# ARTIC_R2_Module.net
KiCad netlist of a schematic drawn in EAGLE
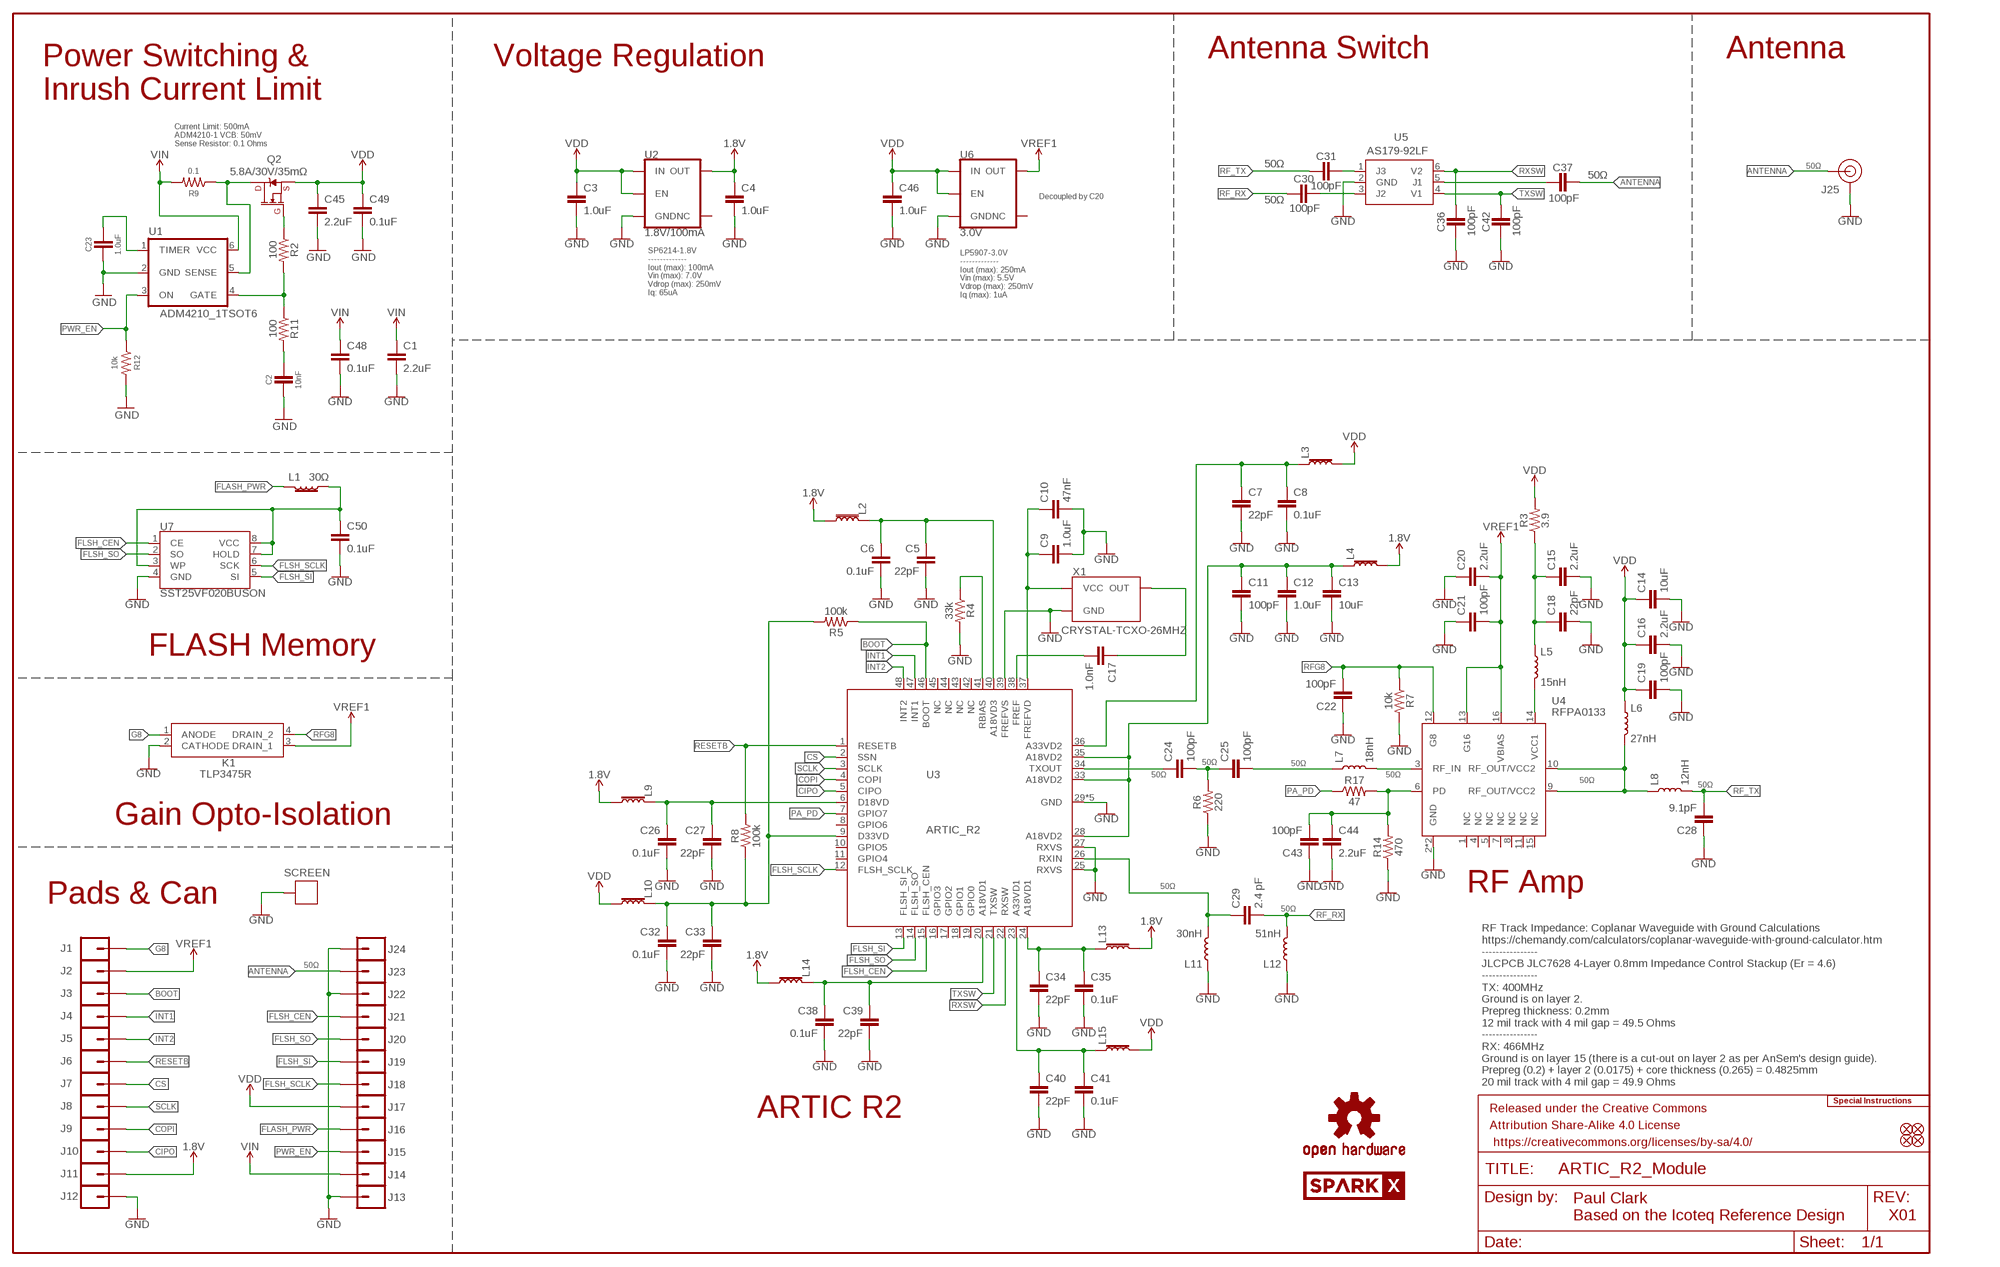
[diagram p0: schematic, sheet 1]

(export (version "E")
  (design (tool "Eeschema 10.0.6"))
  (components
    (comp (ref "C1")
      (value "2.2uF")
      (footprint "eagle-import:0402-TIGHT")
      (libsource (lib "eagle-import") (part "2.2UF-0402_TIGHT-10V-10%-X5R"))
    )
    (comp (ref "C2")
      (value "10nF")
      (footprint "eagle-import:0402-TIGHT")
      (libsource (lib "eagle-import") (part "10NF-0402T-25V-10%"))
    )
    (comp (ref "C3")
      (value "1.0uF")
      (footprint "eagle-import:0402-TIGHT")
      (libsource (lib "eagle-import") (part "1.0UF-0402T-16V-10%"))
    )
    (comp (ref "C4")
      (value "1.0uF")
      (footprint "eagle-import:0402-TIGHT")
      (libsource (lib "eagle-import") (part "1.0UF-0402T-16V-10%"))
    )
    (comp (ref "C5")
      (value "22pF")
      (footprint "eagle-import:0402-TIGHT")
      (libsource (lib "eagle-import") (part "22PF-0402T-16V-10%"))
    )
    (comp (ref "C6")
      (value "0.1uF")
      (footprint "eagle-import:0402-TIGHT")
      (libsource (lib "eagle-import") (part "0.1UF-0402T-6.3V-10%-X7R"))
    )
    (comp (ref "C7")
      (value "22pF")
      (footprint "eagle-import:0402-TIGHT")
      (libsource (lib "eagle-import") (part "22PF-0402T-16V-10%"))
    )
    (comp (ref "C8")
      (value "0.1uF")
      (footprint "eagle-import:0402-TIGHT")
      (libsource (lib "eagle-import") (part "0.1UF-0402T-6.3V-10%-X7R"))
    )
    (comp (ref "C9")
      (value "1.0uF")
      (footprint "eagle-import:0402-TIGHT")
      (libsource (lib "eagle-import") (part "1.0UF-0402T-16V-10%"))
    )
    (comp (ref "C10")
      (value "47nF")
      (footprint "eagle-import:0402-TIGHT")
      (libsource (lib "eagle-import") (part "47NF-0402_TIGHT-25V-10%-X7R"))
    )
    (comp (ref "C11")
      (value "100pF")
      (footprint "eagle-import:0402-TIGHT")
      (libsource (lib "eagle-import") (part "100PF-0402T-50V-5%"))
    )
    (comp (ref "C12")
      (value "1.0uF")
      (footprint "eagle-import:0402-TIGHT")
      (libsource (lib "eagle-import") (part "1.0UF-0402T-16V-10%"))
    )
    (comp (ref "C13")
      (value "10uF")
      (footprint "eagle-import:0402-TIGHT")
      (libsource (lib "eagle-import") (part "10UF-0402T-6.3V-20%"))
    )
    (comp (ref "C14")
      (value "10uF")
      (footprint "eagle-import:0402-TIGHT")
      (libsource (lib "eagle-import") (part "10UF-0402T-6.3V-20%"))
    )
    (comp (ref "C15")
      (value "2.2uF")
      (footprint "eagle-import:0402-TIGHT")
      (libsource (lib "eagle-import") (part "2.2UF-0402_TIGHT-10V-10%-X5R"))
    )
    (comp (ref "C16")
      (value "2.2uF")
      (footprint "eagle-import:0402-TIGHT")
      (libsource (lib "eagle-import") (part "2.2UF-0402_TIGHT-10V-10%-X5R"))
    )
    (comp (ref "C17")
      (value "1.0nF")
      (footprint "eagle-import:0402-TIGHT")
      (libsource (lib "eagle-import") (part "1.0NF/1000PF-0402_TIGHT-50V-10%"))
    )
    (comp (ref "C18")
      (value "22pF")
      (footprint "eagle-import:0402-TIGHT")
      (libsource (lib "eagle-import") (part "22PF-0402T-16V-10%"))
    )
    (comp (ref "C19")
      (value "100pF")
      (footprint "eagle-import:0402-TIGHT")
      (libsource (lib "eagle-import") (part "100PF-0402T-50V-5%"))
    )
    (comp (ref "C20")
      (value "2.2uF")
      (footprint "eagle-import:0402-TIGHT")
      (libsource (lib "eagle-import") (part "2.2UF-0402_TIGHT-10V-10%-X5R"))
    )
    (comp (ref "C21")
      (value "100pF")
      (footprint "eagle-import:0402-TIGHT")
      (libsource (lib "eagle-import") (part "100PF-0402T-50V-5%"))
    )
    (comp (ref "C22")
      (value "100pF")
      (footprint "eagle-import:0402-TIGHT")
      (libsource (lib "eagle-import") (part "100PF-0402T-50V-5%"))
    )
    (comp (ref "C23")
      (value "1.0uF")
      (footprint "eagle-import:0402-TIGHT")
      (libsource (lib "eagle-import") (part "1.0UF-0402T-16V-10%"))
    )
    (comp (ref "C24")
      (value "100pF")
      (footprint "eagle-import:0402-TIGHT")
      (libsource (lib "eagle-import") (part "100PF-0402T-50V-5%"))
    )
    (comp (ref "C25")
      (value "100pF")
      (footprint "eagle-import:0402-TIGHT")
      (libsource (lib "eagle-import") (part "100PF-0402T-50V-5%"))
    )
    (comp (ref "C26")
      (value "0.1uF")
      (footprint "eagle-import:0402-TIGHT")
      (libsource (lib "eagle-import") (part "0.1UF-0402T-6.3V-10%-X7R"))
    )
    (comp (ref "C27")
      (value "22pF")
      (footprint "eagle-import:0402-TIGHT")
      (libsource (lib "eagle-import") (part "22PF-0402T-16V-10%"))
    )
    (comp (ref "C28")
      (value "9.1pF")
      (footprint "eagle-import:0402-TIGHT")
      (fields (field (name "MOUSER_PART") "609-500R07S9R1CV4T"))
      (libsource (lib "eagle-import") (part "9.1PF-0402-TIGHT"))
    )
    (comp (ref "C29")
      (value "2.4 pF")
      (footprint "eagle-import:0402_MURATA")
      (libsource (lib "eagle-import") (part "2.4PF-0402"))
    )
    (comp (ref "C30")
      (value "100pF")
      (footprint "eagle-import:0402-TIGHT")
      (libsource (lib "eagle-import") (part "100PF-0402T-50V-5%"))
    )
    (comp (ref "C31")
      (value "100pF")
      (footprint "eagle-import:0402-TIGHT")
      (libsource (lib "eagle-import") (part "100PF-0402T-50V-5%"))
    )
    (comp (ref "C32")
      (value "0.1uF")
      (footprint "eagle-import:0402-TIGHT")
      (libsource (lib "eagle-import") (part "0.1UF-0402T-6.3V-10%-X7R"))
    )
    (comp (ref "C33")
      (value "22pF")
      (footprint "eagle-import:0402-TIGHT")
      (libsource (lib "eagle-import") (part "22PF-0402T-16V-10%"))
    )
    (comp (ref "C34")
      (value "22pF")
      (footprint "eagle-import:0402-TIGHT")
      (libsource (lib "eagle-import") (part "22PF-0402T-16V-10%"))
    )
    (comp (ref "C35")
      (value "0.1uF")
      (footprint "eagle-import:0402-TIGHT")
      (libsource (lib "eagle-import") (part "0.1UF-0402T-6.3V-10%-X7R"))
    )
    (comp (ref "C36")
      (value "100pF")
      (footprint "eagle-import:0402-TIGHT")
      (libsource (lib "eagle-import") (part "100PF-0402T-50V-5%"))
    )
    (comp (ref "C37")
      (value "100pF")
      (footprint "eagle-import:0402-TIGHT")
      (libsource (lib "eagle-import") (part "100PF-0402T-50V-5%"))
    )
    (comp (ref "C38")
      (value "0.1uF")
      (footprint "eagle-import:0402-TIGHT")
      (libsource (lib "eagle-import") (part "0.1UF-0402T-6.3V-10%-X7R"))
    )
    (comp (ref "C39")
      (value "22pF")
      (footprint "eagle-import:0402-TIGHT")
      (libsource (lib "eagle-import") (part "22PF-0402T-16V-10%"))
    )
    (comp (ref "C40")
      (value "22pF")
      (footprint "eagle-import:0402-TIGHT")
      (libsource (lib "eagle-import") (part "22PF-0402T-16V-10%"))
    )
    (comp (ref "C41")
      (value "0.1uF")
      (footprint "eagle-import:0402-TIGHT")
      (libsource (lib "eagle-import") (part "0.1UF-0402T-6.3V-10%-X7R"))
    )
    (comp (ref "C42")
      (value "100pF")
      (footprint "eagle-import:0402-TIGHT")
      (libsource (lib "eagle-import") (part "100PF-0402T-50V-5%"))
    )
    (comp (ref "C43")
      (value "100pF")
      (footprint "eagle-import:0402-TIGHT")
      (libsource (lib "eagle-import") (part "100PF-0402T-50V-5%"))
    )
    (comp (ref "C44")
      (value "2.2uF")
      (footprint "eagle-import:0402-TIGHT")
      (libsource (lib "eagle-import") (part "2.2UF-0402_TIGHT-10V-10%-X5R"))
    )
    (comp (ref "C45")
      (value "2.2uF")
      (footprint "eagle-import:0402-TIGHT")
      (libsource (lib "eagle-import") (part "2.2UF-0402_TIGHT-10V-10%-X5R"))
    )
    (comp (ref "C46")
      (value "1.0uF")
      (footprint "eagle-import:0402-TIGHT")
      (libsource (lib "eagle-import") (part "1.0UF-0402T-16V-10%"))
    )
    (comp (ref "C48")
      (value "0.1uF")
      (footprint "eagle-import:0402-TIGHT")
      (libsource (lib "eagle-import") (part "0.1UF-0402T-10V-10%-X7R"))
    )
    (comp (ref "C49")
      (value "0.1uF")
      (footprint "eagle-import:0402-TIGHT")
      (libsource (lib "eagle-import") (part "0.1UF-0402T-10V-10%-X7R"))
    )
    (comp (ref "C50")
      (value "0.1uF")
      (footprint "eagle-import:0402-TIGHT")
      (libsource (lib "eagle-import") (part "0.1UF-0402T-6.3V-10%-X7R"))
    )
    (comp (ref "FD1")
      (value "FIDUCIAL1X2")
      (footprint "eagle-import:FIDUCIAL-1X2")
      (libsource (lib "eagle-import") (part "FIDUCIAL1X2"))
    )
    (comp (ref "FD2")
      (value "FIDUCIAL1X2")
      (footprint "eagle-import:FIDUCIAL-1X2")
      (libsource (lib "eagle-import") (part "FIDUCIAL1X2"))
    )
    (comp (ref "FD3")
      (value "FIDUCIAL1X2")
      (footprint "eagle-import:FIDUCIAL-1X2")
      (libsource (lib "eagle-import") (part "FIDUCIAL1X2"))
    )
    (comp (ref "FD4")
      (value "FIDUCIAL1X2")
      (footprint "eagle-import:FIDUCIAL-1X2")
      (libsource (lib "eagle-import") (part "FIDUCIAL1X2"))
    )
    (comp (ref "FRAME1")
      (value "FRAME-LEDGER")
      (footprint "eagle-import:CREATIVE_COMMONS")
      (libsource (lib "eagle-import") (part "FRAME-LEDGER"))
    )
    (comp (ref "J1")
      (value "CONN_01_CASTELLATED_4LAYERWITHOUT_VIA")
      (footprint "eagle-import:CONN_01_CASTELLATED_4LAYER")
      (libsource (lib "eagle-import") (part "CONN_01_CASTELLATED_4LAYERWITHOUT_VIA"))
    )
    (comp (ref "J2")
      (value "CONN_01_CASTELLATED_4LAYERWITHOUT_VIA")
      (footprint "eagle-import:CONN_01_CASTELLATED_4LAYER")
      (libsource (lib "eagle-import") (part "CONN_01_CASTELLATED_4LAYERWITHOUT_VIA"))
    )
    (comp (ref "J3")
      (value "CONN_01_CASTELLATED_4LAYERWITHOUT_VIA")
      (footprint "eagle-import:CONN_01_CASTELLATED_4LAYER")
      (libsource (lib "eagle-import") (part "CONN_01_CASTELLATED_4LAYERWITHOUT_VIA"))
    )
    (comp (ref "J4")
      (value "CONN_01_CASTELLATED_4LAYERWITHOUT_VIA")
      (footprint "eagle-import:CONN_01_CASTELLATED_4LAYER")
      (libsource (lib "eagle-import") (part "CONN_01_CASTELLATED_4LAYERWITHOUT_VIA"))
    )
    (comp (ref "J5")
      (value "CONN_01_CASTELLATED_4LAYERWITHOUT_VIA")
      (footprint "eagle-import:CONN_01_CASTELLATED_4LAYER")
      (libsource (lib "eagle-import") (part "CONN_01_CASTELLATED_4LAYERWITHOUT_VIA"))
    )
    (comp (ref "J6")
      (value "CONN_01_CASTELLATED_4LAYERWITHOUT_VIA")
      (footprint "eagle-import:CONN_01_CASTELLATED_4LAYER")
      (libsource (lib "eagle-import") (part "CONN_01_CASTELLATED_4LAYERWITHOUT_VIA"))
    )
    (comp (ref "J7")
      (value "CONN_01_CASTELLATED_4LAYERWITHOUT_VIA")
      (footprint "eagle-import:CONN_01_CASTELLATED_4LAYER")
      (libsource (lib "eagle-import") (part "CONN_01_CASTELLATED_4LAYERWITHOUT_VIA"))
    )
    (comp (ref "J8")
      (value "CONN_01_CASTELLATED_4LAYERWITHOUT_VIA")
      (footprint "eagle-import:CONN_01_CASTELLATED_4LAYER")
      (libsource (lib "eagle-import") (part "CONN_01_CASTELLATED_4LAYERWITHOUT_VIA"))
    )
    (comp (ref "J9")
      (value "CONN_01_CASTELLATED_4LAYERWITHOUT_VIA")
      (footprint "eagle-import:CONN_01_CASTELLATED_4LAYER")
      (libsource (lib "eagle-import") (part "CONN_01_CASTELLATED_4LAYERWITHOUT_VIA"))
    )
    (comp (ref "J10")
      (value "CONN_01_CASTELLATED_4LAYERWITHOUT_VIA")
      (footprint "eagle-import:CONN_01_CASTELLATED_4LAYER")
      (libsource (lib "eagle-import") (part "CONN_01_CASTELLATED_4LAYERWITHOUT_VIA"))
    )
    (comp (ref "J11")
      (value "CONN_01_CASTELLATED_4LAYERWITHOUT_VIA")
      (footprint "eagle-import:CONN_01_CASTELLATED_4LAYER")
      (libsource (lib "eagle-import") (part "CONN_01_CASTELLATED_4LAYERWITHOUT_VIA"))
    )
    (comp (ref "J12")
      (value "CONN_01_CASTELLATED_4LAYERWITHOUT_VIA")
      (footprint "eagle-import:CONN_01_CASTELLATED_4LAYER")
      (libsource (lib "eagle-import") (part "CONN_01_CASTELLATED_4LAYERWITHOUT_VIA"))
    )
    (comp (ref "J13")
      (value "CONN_01_CASTELLATED_4LAYERWITHOUT_VIA")
      (footprint "eagle-import:CONN_01_CASTELLATED_4LAYER")
      (libsource (lib "eagle-import") (part "CONN_01_CASTELLATED_4LAYERWITHOUT_VIA"))
    )
    (comp (ref "J14")
      (value "CONN_01_CASTELLATED_4LAYERWITHOUT_VIA")
      (footprint "eagle-import:CONN_01_CASTELLATED_4LAYER")
      (libsource (lib "eagle-import") (part "CONN_01_CASTELLATED_4LAYERWITHOUT_VIA"))
    )
    (comp (ref "J15")
      (value "CONN_01_CASTELLATED_4LAYERWITHOUT_VIA")
      (footprint "eagle-import:CONN_01_CASTELLATED_4LAYER")
      (libsource (lib "eagle-import") (part "CONN_01_CASTELLATED_4LAYERWITHOUT_VIA"))
    )
    (comp (ref "J16")
      (value "CONN_01_CASTELLATED_4LAYERWITHOUT_VIA")
      (footprint "eagle-import:CONN_01_CASTELLATED_4LAYER")
      (libsource (lib "eagle-import") (part "CONN_01_CASTELLATED_4LAYERWITHOUT_VIA"))
    )
    (comp (ref "J17")
      (value "CONN_01_CASTELLATED_4LAYERWITHOUT_VIA")
      (footprint "eagle-import:CONN_01_CASTELLATED_4LAYER")
      (libsource (lib "eagle-import") (part "CONN_01_CASTELLATED_4LAYERWITHOUT_VIA"))
    )
    (comp (ref "J18")
      (value "CONN_01_CASTELLATED_4LAYERWITHOUT_VIA")
      (footprint "eagle-import:CONN_01_CASTELLATED_4LAYER")
      (libsource (lib "eagle-import") (part "CONN_01_CASTELLATED_4LAYERWITHOUT_VIA"))
    )
    (comp (ref "J19")
      (value "CONN_01_CASTELLATED_4LAYERWITHOUT_VIA")
      (footprint "eagle-import:CONN_01_CASTELLATED_4LAYER")
      (libsource (lib "eagle-import") (part "CONN_01_CASTELLATED_4LAYERWITHOUT_VIA"))
    )
    (comp (ref "J20")
      (value "CONN_01_CASTELLATED_4LAYERWITHOUT_VIA")
      (footprint "eagle-import:CONN_01_CASTELLATED_4LAYER")
      (libsource (lib "eagle-import") (part "CONN_01_CASTELLATED_4LAYERWITHOUT_VIA"))
    )
    (comp (ref "J21")
      (value "CONN_01_CASTELLATED_4LAYERWITHOUT_VIA")
      (footprint "eagle-import:CONN_01_CASTELLATED_4LAYER")
      (libsource (lib "eagle-import") (part "CONN_01_CASTELLATED_4LAYERWITHOUT_VIA"))
    )
    (comp (ref "J22")
      (value "CONN_01_CASTELLATED_4LAYERWITHOUT_VIA")
      (footprint "eagle-import:CONN_01_CASTELLATED_4LAYER")
      (libsource (lib "eagle-import") (part "CONN_01_CASTELLATED_4LAYERWITHOUT_VIA"))
    )
    (comp (ref "J23")
      (value "CONN_01_CASTELLATED_4LAYERWITHOUT_VIA")
      (footprint "eagle-import:CONN_01_CASTELLATED_4LAYER")
      (libsource (lib "eagle-import") (part "CONN_01_CASTELLATED_4LAYERWITHOUT_VIA"))
    )
    (comp (ref "J24")
      (value "CONN_01_CASTELLATED_4LAYERWITHOUT_VIA")
      (footprint "eagle-import:CONN_01_CASTELLATED_4LAYER")
      (libsource (lib "eagle-import") (part "CONN_01_CASTELLATED_4LAYERWITHOUT_VIA"))
    )
    (comp (ref "J25")
      (value "U.FL")
      (footprint "eagle-import:U.FL_REDUCED_FOOTPRINT")
      (libsource (lib "eagle-import") (part "U.FL2PIN-REDUCED-FOOTPRINT"))
    )
    (comp (ref "K1")
      (value "TLP3475R")
      (footprint "eagle-import:TLP3475RTPF")
      (fields (field (name "DIGIKEY_PART") "TLP3475R(TPFCT-ND - Cut Tape (CT)"))
      (libsource (lib "eagle-import") (part "TLP3475R"))
    )
    (comp (ref "L1")
      (value "30Ω")
      (footprint "eagle-import:0402-TIGHT")
      (libsource (lib "eagle-import") (part "FERRITE_BEAD-0402-30OHM-100MHZ"))
    )
    (comp (ref "L2")
      (value "30Ω")
      (footprint "eagle-import:0402-TIGHT")
      (libsource (lib "eagle-import") (part "FERRITE_BEAD-0402-30OHM-100MHZ"))
    )
    (comp (ref "L3")
      (value "30Ω")
      (footprint "eagle-import:0402-TIGHT")
      (libsource (lib "eagle-import") (part "FERRITE_BEAD-0402-30OHM-100MHZ"))
    )
    (comp (ref "L4")
      (value "30Ω")
      (footprint "eagle-import:0402-TIGHT")
      (libsource (lib "eagle-import") (part "FERRITE_BEAD-0402-30OHM-100MHZ"))
    )
    (comp (ref "L5")
      (value "15nH")
      (footprint "eagle-import:0402_COILCRAFT")
      (fields (field (name "MOUSER_PART") "994-0402HP-15NXGLU"))
      (libsource (lib "eagle-import") (part "15NH-0402"))
    )
    (comp (ref "L6")
      (value "27nH")
      (footprint "eagle-import:0402_COILCRAFT")
      (fields (field (name "MOUSER_PART") "994-0402HP-27NXGLU"))
      (libsource (lib "eagle-import") (part "27NH-0402"))
    )
    (comp (ref "L7")
      (value "18nH")
      (footprint "eagle-import:0402_COILCRAFT")
      (fields (field (name "MOUSER_PART") "994-0402HP-18NXGLU"))
      (libsource (lib "eagle-import") (part "18NH-0402"))
    )
    (comp (ref "L8")
      (value "12nH")
      (footprint "eagle-import:0402_COILCRAFT")
      (fields (field (name "MOUSER_PART") "994-0402HP-12NXGLU"))
      (libsource (lib "eagle-import") (part "12NH-0402"))
    )
    (comp (ref "L9")
      (value "30Ω")
      (footprint "eagle-import:0402-TIGHT")
      (libsource (lib "eagle-import") (part "FERRITE_BEAD-0402-30OHM-100MHZ"))
    )
    (comp (ref "L10")
      (value "30Ω")
      (footprint "eagle-import:0402-TIGHT")
      (libsource (lib "eagle-import") (part "FERRITE_BEAD-0402-30OHM-100MHZ"))
    )
    (comp (ref "L11")
      (value "30nH")
      (footprint "eagle-import:0402_COILCRAFT")
      (fields (field (name "MOUSER_PART") "994-0402HP-30NXGLU"))
      (libsource (lib "eagle-import") (part "30NH-0402"))
    )
    (comp (ref "L12")
      (value "51nH")
      (footprint "eagle-import:0402_COILCRAFT")
      (fields (field (name "MOUSER_PART") "994-0402HP-51NXGLU"))
      (libsource (lib "eagle-import") (part "51NH-0402"))
    )
    (comp (ref "L13")
      (value "30Ω")
      (footprint "eagle-import:0402-TIGHT")
      (libsource (lib "eagle-import") (part "FERRITE_BEAD-0402-30OHM-100MHZ"))
    )
    (comp (ref "L14")
      (value "30Ω")
      (footprint "eagle-import:0402-TIGHT")
      (libsource (lib "eagle-import") (part "FERRITE_BEAD-0402-30OHM-100MHZ"))
    )
    (comp (ref "L15")
      (value "30Ω")
      (footprint "eagle-import:0402-TIGHT")
      (libsource (lib "eagle-import") (part "FERRITE_BEAD-0402-30OHM-100MHZ"))
    )
    (comp (ref "LOGO1")
      (value "SPECIAL_INSTRUCTIONS-ORDERING")
      (footprint "eagle-import:ORDERING_INSTRUCTIONS")
      (libsource (lib "eagle-import") (part "SPECIAL_INSTRUCTIONS-ORDERING"))
    )
    (comp (ref "LOGO3")
      (value "OSHW-LOGOS")
      (footprint "eagle-import:OSHW-LOGO-S")
      (libsource (lib "eagle-import") (part "OSHW-LOGOS"))
    )
    (comp (ref "Q2")
      (value "5.8A/30V/35mΩ")
      (footprint "eagle-import:SOT23-3")
      (libsource (lib "eagle-import") (part "MOSFET-NCH-AO3404A"))
    )
    (comp (ref "R2")
      (value "100")
      (footprint "eagle-import:0402-TIGHT")
      (libsource (lib "eagle-import") (part "100OHM-0402-TIGHT-1/16W-1%"))
    )
    (comp (ref "R3")
      (value "3.9")
      (footprint "eagle-import:0402-TIGHT")
      (libsource (lib "eagle-import") (part "3.9OHM-0402-TIGHT-1/16W-1%"))
    )
    (comp (ref "R4")
      (value "33k")
      (footprint "eagle-import:0402-TIGHT")
      (libsource (lib "eagle-import") (part "33KOHM-0402T-1/16W-1%"))
    )
    (comp (ref "R5")
      (value "100k")
      (footprint "eagle-import:0402-TIGHT")
      (libsource (lib "eagle-import") (part "100KOHM-0402T-1/16W-1%"))
    )
    (comp (ref "R6")
      (value "220")
      (footprint "eagle-import:0402-TIGHT")
      (libsource (lib "eagle-import") (part "220OHM-0402-TIGHT-1/16W-1%"))
    )
    (comp (ref "R7")
      (value "10k")
      (footprint "eagle-import:0402-TIGHT")
      (libsource (lib "eagle-import") (part "10KOHM-0402T-1/16W-1%"))
    )
    (comp (ref "R8")
      (value "100k")
      (footprint "eagle-import:0402-TIGHT")
      (libsource (lib "eagle-import") (part "100KOHM-0402T-1/16W-1%"))
    )
    (comp (ref "R9")
      (value "0.1")
      (footprint "eagle-import:0603")
      (libsource (lib "eagle-import") (part "0.1OHM-0603-1/3W-1%"))
    )
    (comp (ref "R11")
      (value "100")
      (footprint "eagle-import:0402-TIGHT")
      (libsource (lib "eagle-import") (part "100OHM-0402-TIGHT-1/16W-1%"))
    )
    (comp (ref "R12")
      (value "10k")
      (footprint "eagle-import:0402-TIGHT")
      (libsource (lib "eagle-import") (part "10KOHM-0402T-1/16W-1%"))
    )
    (comp (ref "R14")
      (value "470")
      (footprint "eagle-import:0402-TIGHT")
      (libsource (lib "eagle-import") (part "470OHM-0402-TIGHT-1/16W-1%"))
    )
    (comp (ref "R17")
      (value "47")
      (footprint "eagle-import:0402-TIGHT")
      (libsource (lib "eagle-import") (part "47OHM-0402-TIGHT-1/16W-1%"))
    )
    (comp (ref "SCREEN")
      (value "IOTA_SCREENING_CANSTRAIGHT_SLOTS")
      (footprint "eagle-import:IOTA_CAN_STRAIGHT_SLOTS")
      (libsource (lib "eagle-import") (part "IOTA_SCREENING_CANSTRAIGHT_SLOTS"))
    )
    (comp (ref "SPARKX2")
      (value "SPARKX-LOGO4")
      (footprint "eagle-import:SPARKX-MEDIUM")
      (libsource (lib "eagle-import") (part "SPARKX-LOGO4"))
    )
    (comp (ref "U1")
      (value "ADM4210_1TSOT6")
      (footprint "eagle-import:TSOT6")
      (libsource (lib "eagle-import") (part "ADM4210_1TSOT6"))
    )
    (comp (ref "U2")
      (value "1.8V/100mA")
      (footprint "eagle-import:SC70")
      (libsource (lib "eagle-import") (part "V_REG_SP6214-1.8V"))
    )
    (comp (ref "U3")
      (value "ARTIC_R2")
      (footprint "eagle-import:QFN-48")
      (libsource (lib "eagle-import") (part "ARTIC_R2"))
    )
    (comp (ref "U4")
      (value "RFPA0133")
      (footprint "eagle-import:QFN50P300X300X86-17N")
      (fields
        (field (name "MANUFACTURER_PART_NUMBER") "RFPA0133TR7")
        (field (name "MOUSER_PART_NUMBER") "772-RFPA0133")
      )
      (libsource (lib "eagle-import") (part "RFPA0133"))
    )
    (comp (ref "U5")
      (value "AS179-92LF")
      (footprint "eagle-import:SOT65P220X100-6N")
      (libsource (lib "eagle-import") (part "AS179-92LF"))
    )
    (comp (ref "U6")
      (value "3.0V")
      (footprint "eagle-import:SOT23-5")
      (fields
        (field (name "DIGIKEY_PART") "296-40357-1-ND")
        (field (name "MANU_PART") "LP5907MFX-3.0/NOPB")
        (field (name "MOUSER_PART") "595-LP5907MFX-3.0NPB")
      )
      (libsource (lib "eagle-import") (part "V_REG_LP5907SOT23-3.0V"))
    )
    (comp (ref "U7")
      (value "SST25VF020BUSON")
      (footprint "eagle-import:USON_3X2MM")
      (fields
        (field (name "DIGIKEY_PART") "SST25VF020B-80-4I-Q3AE-TCT-ND")
        (field (name "MANU_PART") "SST25VF020B-80-4I-Q3AE-T")
      )
      (libsource (lib "eagle-import") (part "SST25VF020BUSON"))
    )
    (comp (ref "X1")
      (value "CRYSTAL-TCXO-26MHZ")
      (footprint "eagle-import:CRYSTAL-TCXO-SMD-1.65X1.25")
      (fields (field (name "MOUSER_PART") "449-LFTCXO073004CUTT"))
      (libsource (lib "eagle-import") (part "CRYSTAL-TCXO-26MHZ"))
    )
  )
  (nets
    (net (code "1") (name "1.8V") (class "Default")
      (node (ref "C4") (pin "1") (pinfunction "1_1") (pintype "passive"))
      (node (ref "J11") (pin "1") (pinfunction "1_1") (pintype "passive"))
      (node (ref "L13") (pin "2") (pinfunction "2_2") (pintype "passive"))
      (node (ref "L14") (pin "2") (pinfunction "2_2") (pintype "passive"))
      (node (ref "L2") (pin "2") (pinfunction "2_2") (pintype "passive"))
      (node (ref "L4") (pin "2") (pinfunction "2_2") (pintype "passive"))
      (node (ref "L9") (pin "2") (pinfunction "2_2") (pintype "passive"))
      (node (ref "U2") (pin "5") (pinfunction "OUT_5") (pintype "passive"))
    )
    (net (code "2") (name "ANTENNA") (class "Default")
      (node (ref "C37") (pin "1") (pinfunction "1_1") (pintype "passive"))
      (node (ref "J23") (pin "1") (pinfunction "1_1") (pintype "passive"))
      (node (ref "J25") (pin "FEED") (pinfunction "SIGNAL_FEED") (pintype "bidirectional"))
    )
    (net (code "3") (name "BOOT") (class "Default")
      (node (ref "J3") (pin "1") (pinfunction "1_1") (pintype "passive"))
      (node (ref "R5") (pin "1") (pinfunction "1_1") (pintype "passive"))
      (node (ref "U3") (pin "46") (pinfunction "BOOT_46") (pintype "bidirectional"))
    )
    (net (code "4") (name "CIPO") (class "Default")
      (node (ref "J10") (pin "1") (pinfunction "1_1") (pintype "passive"))
      (node (ref "U3") (pin "5") (pinfunction "CIPO_5") (pintype "bidirectional"))
    )
    (net (code "5") (name "COPI") (class "Default")
      (node (ref "J9") (pin "1") (pinfunction "1_1") (pintype "passive"))
      (node (ref "U3") (pin "4") (pinfunction "COPI_4") (pintype "bidirectional"))
    )
    (net (code "6") (name "CS") (class "Default")
      (node (ref "J7") (pin "1") (pinfunction "1_1") (pintype "passive"))
      (node (ref "U3") (pin "2") (pinfunction "SSN_2") (pintype "bidirectional"))
    )
    (net (code "7") (name "FLASH_PWR") (class "Default")
      (node (ref "J16") (pin "1") (pinfunction "1_1") (pintype "passive"))
      (node (ref "L1") (pin "2") (pinfunction "2_2") (pintype "passive"))
    )
    (net (code "8") (name "FLSH_CEN") (class "Default")
      (node (ref "J21") (pin "1") (pinfunction "1_1") (pintype "passive"))
      (node (ref "U3") (pin "15") (pinfunction "FLSH_CEN_15") (pintype "bidirectional"))
      (node (ref "U7") (pin "1") (pinfunction "CE_1") (pintype "bidirectional"))
    )
    (net (code "9") (name "FLSH_SCLK") (class "Default")
      (node (ref "J18") (pin "1") (pinfunction "1_1") (pintype "passive"))
      (node (ref "U3") (pin "12") (pinfunction "FLSH_SCLK_12") (pintype "bidirectional"))
      (node (ref "U7") (pin "6") (pinfunction "SCK_6") (pintype "bidirectional"))
    )
    (net (code "10") (name "FLSH_SI") (class "Default")
      (node (ref "J19") (pin "1") (pinfunction "1_1") (pintype "passive"))
      (node (ref "U3") (pin "13") (pinfunction "FLSH_SI_13") (pintype "bidirectional"))
      (node (ref "U7") (pin "5") (pinfunction "SI_5") (pintype "bidirectional"))
    )
    (net (code "11") (name "FLSH_SO") (class "Default")
      (node (ref "J20") (pin "1") (pinfunction "1_1") (pintype "passive"))
      (node (ref "U3") (pin "14") (pinfunction "FLSH_SO_14") (pintype "bidirectional"))
      (node (ref "U7") (pin "2") (pinfunction "SO_2") (pintype "bidirectional"))
    )
    (net (code "12") (name "G8") (class "Default")
      (node (ref "J1") (pin "1") (pinfunction "1_1") (pintype "passive"))
      (node (ref "K1") (pin "1") (pinfunction "ANODE_1") (pintype "bidirectional"))
    )
    (net (code "13") (name "GND") (class "Default")
      (node (ref "C1") (pin "2") (pinfunction "2_2") (pintype "passive"))
      (node (ref "C10") (pin "2") (pinfunction "2_2") (pintype "passive"))
      (node (ref "C11") (pin "2") (pinfunction "2_2") (pintype "passive"))
      (node (ref "C12") (pin "2") (pinfunction "2_2") (pintype "passive"))
      (node (ref "C13") (pin "2") (pinfunction "2_2") (pintype "passive"))
      (node (ref "C14") (pin "2") (pinfunction "2_2") (pintype "passive"))
      (node (ref "C15") (pin "2") (pinfunction "2_2") (pintype "passive"))
      (node (ref "C16") (pin "2") (pinfunction "2_2") (pintype "passive"))
      (node (ref "C18") (pin "2") (pinfunction "2_2") (pintype "passive"))
      (node (ref "C19") (pin "2") (pinfunction "2_2") (pintype "passive"))
      (node (ref "C2") (pin "2") (pinfunction "2_2") (pintype "passive"))
      (node (ref "C20") (pin "1") (pinfunction "1_1") (pintype "passive"))
      (node (ref "C21") (pin "1") (pinfunction "1_1") (pintype "passive"))
      (node (ref "C22") (pin "1") (pinfunction "1_1") (pintype "passive"))
      (node (ref "C23") (pin "2") (pinfunction "2_2") (pintype "passive"))
      (node (ref "C26") (pin "2") (pinfunction "2_2") (pintype "passive"))
      (node (ref "C27") (pin "2") (pinfunction "2_2") (pintype "passive"))
      (node (ref "C28") (pin "1") (pinfunction "1_1") (pintype "passive"))
      (node (ref "C3") (pin "2") (pinfunction "2_2") (pintype "passive"))
      (node (ref "C32") (pin "2") (pinfunction "2_2") (pintype "passive"))
      (node (ref "C33") (pin "2") (pinfunction "2_2") (pintype "passive"))
      (node (ref "C34") (pin "2") (pinfunction "2_2") (pintype "passive"))
      (node (ref "C35") (pin "2") (pinfunction "2_2") (pintype "passive"))
      (node (ref "C36") (pin "2") (pinfunction "2_2") (pintype "passive"))
      (node (ref "C38") (pin "2") (pinfunction "2_2") (pintype "passive"))
      (node (ref "C39") (pin "2") (pinfunction "2_2") (pintype "passive"))
      (node (ref "C4") (pin "2") (pinfunction "2_2") (pintype "passive"))
      (node (ref "C40") (pin "2") (pinfunction "2_2") (pintype "passive"))
      (node (ref "C41") (pin "2") (pinfunction "2_2") (pintype "passive"))
      (node (ref "C42") (pin "2") (pinfunction "2_2") (pintype "passive"))
      (node (ref "C43") (pin "1") (pinfunction "1_1") (pintype "passive"))
      (node (ref "C44") (pin "2") (pinfunction "2_2") (pintype "passive"))
      (node (ref "C45") (pin "2") (pinfunction "2_2") (pintype "passive"))
      (node (ref "C46") (pin "2") (pinfunction "2_2") (pintype "passive"))
      (node (ref "C48") (pin "2") (pinfunction "2_2") (pintype "passive"))
      (node (ref "C49") (pin "2") (pinfunction "2_2") (pintype "passive"))
      (node (ref "C5") (pin "2") (pinfunction "2_2") (pintype "passive"))
      (node (ref "C50") (pin "2") (pinfunction "2_2") (pintype "passive"))
      (node (ref "C6") (pin "2") (pinfunction "2_2") (pintype "passive"))
      (node (ref "C7") (pin "2") (pinfunction "2_2") (pintype "passive"))
      (node (ref "C8") (pin "2") (pinfunction "2_2") (pintype "passive"))
      (node (ref "C9") (pin "2") (pinfunction "2_2") (pintype "passive"))
      (node (ref "J12") (pin "1") (pinfunction "1_1") (pintype "passive"))
      (node (ref "J13") (pin "1") (pinfunction "1_1") (pintype "passive"))
      (node (ref "J22") (pin "1") (pinfunction "1_1") (pintype "passive"))
      (node (ref "J24") (pin "1") (pinfunction "1_1") (pintype "passive"))
      (node (ref "J25") (pin "1") (pinfunction "GND_1") (pintype "bidirectional"))
      (node (ref "J25") (pin "2") (pinfunction "GND_2") (pintype "bidirectional"))
      (node (ref "K1") (pin "2") (pinfunction "CATHODE_2") (pintype "bidirectional"))
      (node (ref "L11") (pin "P$1") (pinfunction "1_P$1") (pintype "passive"))
      (node (ref "L12") (pin "P$1") (pinfunction "1_P$1") (pintype "passive"))
      (node (ref "R12") (pin "2") (pinfunction "2_2") (pintype "passive"))
      (node (ref "R14") (pin "1") (pinfunction "1_1") (pintype "passive"))
      (node (ref "R4") (pin "2") (pinfunction "2_2") (pintype "passive"))
      (node (ref "R6") (pin "1") (pinfunction "1_1") (pintype "passive"))
      (node (ref "R7") (pin "2") (pinfunction "2_2") (pintype "passive"))
      (node (ref "SCREEN") (pin "1-1") (pinfunction "P$1_1-1") (pintype "bidirectional"))
      (node (ref "SCREEN") (pin "1-16") (pinfunction "P$1_1-16") (pintype "bidirectional"))
      (node (ref "SCREEN") (pin "2") (pinfunction "P$1_2") (pintype "bidirectional"))
      (node (ref "SCREEN") (pin "3-1") (pinfunction "P$1_3-1") (pintype "bidirectional"))
      (node (ref "SCREEN") (pin "3-16") (pinfunction "P$1_3-16") (pintype "bidirectional"))
      (node (ref "SCREEN") (pin "4") (pinfunction "P$1_4") (pintype "bidirectional"))
      (node (ref "U1") (pin "2") (pinfunction "GND_2") (pintype "power_in"))
      (node (ref "U2") (pin "2") (pinfunction "GND_2") (pintype "input"))
      (node (ref "U3") (pin "25") (pinfunction "RXVS_25") (pintype "bidirectional"))
      (node (ref "U3") (pin "27") (pinfunction "RXVS_27") (pintype "bidirectional"))
      (node (ref "U3") (pin "29") (pinfunction "GND_29") (pintype "bidirectional"))
      (node (ref "U3") (pin "30") (pinfunction "GND_30") (pintype "bidirectional"))
      (node (ref "U3") (pin "31") (pinfunction "GND_31") (pintype "bidirectional"))
      (node (ref "U3") (pin "32") (pinfunction "GND_32") (pintype "bidirectional"))
      (node (ref "U3") (pin "39") (pinfunction "FREFVS_39") (pintype "bidirectional"))
      (node (ref "U3") (pin "GND") (pinfunction "GND_GND") (pintype "bidirectional"))
      (node (ref "U4") (pin "2") (pinfunction "GND_2") (pintype "power_in"))
      (node (ref "U4") (pin "EDAP") (pinfunction "GND_EDAP") (pintype "power_in"))
      (node (ref "U5") (pin "2") (pinfunction "GND_2") (pintype "power_in"))
      (node (ref "U6") (pin "2") (pinfunction "GND_2") (pintype "input"))
      (node (ref "U7") (pin "4") (pinfunction "GND_4") (pintype "power_in"))
      (node (ref "X1") (pin "1") (pinfunction "GND_1") (pintype "bidirectional"))
      (node (ref "X1") (pin "2") (pinfunction "GND_2") (pintype "bidirectional"))
    )
    (net (code "14") (name "INT1") (class "Default")
      (node (ref "J4") (pin "1") (pinfunction "1_1") (pintype "passive"))
      (node (ref "U3") (pin "47") (pinfunction "INT1_47") (pintype "bidirectional"))
    )
    (net (code "15") (name "INT2") (class "Default")
      (node (ref "J5") (pin "1") (pinfunction "1_1") (pintype "passive"))
      (node (ref "U3") (pin "48") (pinfunction "INT2_48") (pintype "bidirectional"))
    )
    (net (code "16") (name "Net-(C2-Pad1)") (class "Default")
      (node (ref "C2") (pin "1") (pinfunction "1_1") (pintype "passive"))
      (node (ref "R11") (pin "2") (pinfunction "2_2") (pintype "passive"))
    )
    (net (code "17") (name "Net-(C11-Pad1)") (class "Default")
      (node (ref "C11") (pin "1") (pinfunction "1_1") (pintype "passive"))
      (node (ref "C12") (pin "1") (pinfunction "1_1") (pintype "passive"))
      (node (ref "C13") (pin "1") (pinfunction "1_1") (pintype "passive"))
      (node (ref "L4") (pin "1") (pinfunction "1_1") (pintype "passive"))
      (node (ref "U3") (pin "28") (pinfunction "A18VD2_28") (pintype "power_in"))
      (node (ref "U3") (pin "33") (pinfunction "A18VD2_33") (pintype "power_in"))
      (node (ref "U3") (pin "35") (pinfunction "A18VD2_35") (pintype "power_in"))
    )
    (net (code "18") (name "Net-(C24-Pad2)") (class "Default")
      (node (ref "C24") (pin "2") (pinfunction "2_2") (pintype "passive"))
      (node (ref "C25") (pin "1") (pinfunction "1_1") (pintype "passive"))
      (node (ref "R6") (pin "2") (pinfunction "2_2") (pintype "passive"))
    )
    (net (code "19") (name "Net-(C29-1)") (class "Default")
      (node (ref "C29") (pin "P$1") (pinfunction "1_P$1") (pintype "passive"))
      (node (ref "L11") (pin "P$2") (pinfunction "2_P$2") (pintype "passive"))
      (node (ref "U3") (pin "26") (pinfunction "RXIN_26") (pintype "bidirectional"))
    )
    (net (code "20") (name "Net-(C34-Pad1)") (class "Default")
      (node (ref "C34") (pin "1") (pinfunction "1_1") (pintype "passive"))
      (node (ref "C35") (pin "1") (pinfunction "1_1") (pintype "passive"))
      (node (ref "L13") (pin "1") (pinfunction "1_1") (pintype "passive"))
      (node (ref "U3") (pin "24") (pinfunction "A18VD1_24") (pintype "power_in"))
    )
    (net (code "21") (name "Net-(C38-Pad1)") (class "Default")
      (node (ref "C38") (pin "1") (pinfunction "1_1") (pintype "passive"))
      (node (ref "C39") (pin "1") (pinfunction "1_1") (pintype "passive"))
      (node (ref "L14") (pin "1") (pinfunction "1_1") (pintype "passive"))
      (node (ref "U3") (pin "20") (pinfunction "A18VD1_20") (pintype "power_in"))
    )
    (net (code "22") (name "Net-(L5-1)") (class "Default")
      (node (ref "C15") (pin "1") (pinfunction "1_1") (pintype "passive"))
      (node (ref "C18") (pin "1") (pinfunction "1_1") (pintype "passive"))
      (node (ref "L5") (pin "P$1") (pinfunction "1_P$1") (pintype "passive"))
      (node (ref "R3") (pin "1") (pinfunction "1_1") (pintype "passive"))
    )
    (net (code "23") (name "Net-(L5-2)") (class "Default")
      (node (ref "L5") (pin "P$2") (pinfunction "2_P$2") (pintype "passive"))
      (node (ref "U4") (pin "14") (pinfunction "VCC1_14") (pintype "power_in"))
    )
    (net (code "24") (name "Net-(L6-2)") (class "Default")
      (node (ref "L6") (pin "P$2") (pinfunction "2_P$2") (pintype "passive"))
      (node (ref "L8") (pin "P$1") (pinfunction "1_P$1") (pintype "passive"))
      (node (ref "U4") (pin "10") (pinfunction "RF_OUT/VCC2_10") (pintype "output"))
      (node (ref "U4") (pin "9") (pinfunction "RF_OUT/VCC2_9") (pintype "output"))
    )
    (net (code "25") (name "Net-(L7-1)") (class "Default")
      (node (ref "C25") (pin "2") (pinfunction "2_2") (pintype "passive"))
      (node (ref "L7") (pin "P$1") (pinfunction "1_P$1") (pintype "passive"))
    )
    (net (code "26") (name "Net-(L7-2)") (class "Default")
      (node (ref "L7") (pin "P$2") (pinfunction "2_P$2") (pintype "passive"))
      (node (ref "U4") (pin "3") (pinfunction "RF_IN_3") (pintype "input"))
    )
    (net (code "27") (name "Net-(Q2-D)") (class "Default")
      (node (ref "Q2") (pin "3") (pinfunction "D_3") (pintype "bidirectional"))
      (node (ref "R9") (pin "1") (pinfunction "1_1") (pintype "passive"))
      (node (ref "U1") (pin "5") (pinfunction "SENSE_5") (pintype "input"))
    )
    (net (code "28") (name "Net-(Q2-G)") (class "Default")
      (node (ref "Q2") (pin "1") (pinfunction "G_1") (pintype "bidirectional"))
      (node (ref "R2") (pin "1") (pinfunction "1_1") (pintype "passive"))
    )
    (net (code "29") (name "Net-(U1-GATE)") (class "Default")
      (node (ref "R11") (pin "1") (pinfunction "1_1") (pintype "passive"))
      (node (ref "R2") (pin "2") (pinfunction "2_2") (pintype "passive"))
      (node (ref "U1") (pin "4") (pinfunction "GATE_4") (pintype "output"))
    )
    (net (code "30") (name "Net-(U1-TIMER)") (class "Default")
      (node (ref "C23") (pin "1") (pinfunction "1_1") (pintype "passive"))
      (node (ref "U1") (pin "1") (pinfunction "TIMER_1") (pintype "input"))
    )
    (net (code "31") (name "Net-(U3-A18VD3)") (class "Default")
      (node (ref "C5") (pin "1") (pinfunction "1_1") (pintype "passive"))
      (node (ref "C6") (pin "1") (pinfunction "1_1") (pintype "passive"))
      (node (ref "L2") (pin "1") (pinfunction "1_1") (pintype "passive"))
      (node (ref "U3") (pin "40") (pinfunction "A18VD3_40") (pintype "power_in"))
    )
    (net (code "32") (name "Net-(U3-A33VD1)") (class "Default")
      (node (ref "C40") (pin "1") (pinfunction "1_1") (pintype "passive"))
      (node (ref "C41") (pin "1") (pinfunction "1_1") (pintype "passive"))
      (node (ref "L15") (pin "1") (pinfunction "1_1") (pintype "passive"))
      (node (ref "U3") (pin "23") (pinfunction "A33VD1_23") (pintype "power_in"))
    )
    (net (code "33") (name "Net-(U3-A33VD2)") (class "Default")
      (node (ref "C7") (pin "1") (pinfunction "1_1") (pintype "passive"))
      (node (ref "C8") (pin "1") (pinfunction "1_1") (pintype "passive"))
      (node (ref "L3") (pin "1") (pinfunction "1_1") (pintype "passive"))
      (node (ref "U3") (pin "36") (pinfunction "A33VD2_36") (pintype "power_in"))
    )
    (net (code "34") (name "Net-(U3-D18VD)") (class "Default")
      (node (ref "C26") (pin "1") (pinfunction "1_1") (pintype "passive"))
      (node (ref "C27") (pin "1") (pinfunction "1_1") (pintype "passive"))
      (node (ref "L9") (pin "1") (pinfunction "1_1") (pintype "passive"))
      (node (ref "U3") (pin "6") (pinfunction "D18VD_6") (pintype "power_in"))
    )
    (net (code "35") (name "Net-(U3-D33VD)") (class "Default")
      (node (ref "C32") (pin "1") (pinfunction "1_1") (pintype "passive"))
      (node (ref "C33") (pin "1") (pinfunction "1_1") (pintype "passive"))
      (node (ref "L10") (pin "1") (pinfunction "1_1") (pintype "passive"))
      (node (ref "R5") (pin "2") (pinfunction "2_2") (pintype "passive"))
      (node (ref "R8") (pin "1") (pinfunction "1_1") (pintype "passive"))
      (node (ref "U3") (pin "9") (pinfunction "D33VD_9") (pintype "power_in"))
    )
    (net (code "36") (name "Net-(U3-FREF)") (class "Default")
      (node (ref "C17") (pin "2") (pinfunction "2_2") (pintype "passive"))
      (node (ref "U3") (pin "38") (pinfunction "FREF_38") (pintype "bidirectional"))
    )
    (net (code "37") (name "Net-(U3-FREFVD)") (class "Default")
      (node (ref "C10") (pin "1") (pinfunction "1_1") (pintype "passive"))
      (node (ref "C9") (pin "1") (pinfunction "1_1") (pintype "passive"))
      (node (ref "U3") (pin "37") (pinfunction "FREFVD_37") (pintype "bidirectional"))
      (node (ref "X1") (pin "4") (pinfunction "VCC_4") (pintype "bidirectional"))
    )
    (net (code "38") (name "Net-(U3-RBIAS)") (class "Default")
      (node (ref "R4") (pin "1") (pinfunction "1_1") (pintype "passive"))
      (node (ref "U3") (pin "41") (pinfunction "RBIAS_41") (pintype "bidirectional"))
    )
    (net (code "39") (name "Net-(U3-TXOUT)") (class "Default")
      (node (ref "C24") (pin "1") (pinfunction "1_1") (pintype "passive"))
      (node (ref "U3") (pin "34") (pinfunction "TXOUT_34") (pintype "bidirectional"))
    )
    (net (code "40") (name "Net-(U4-PD)") (class "Default")
      (node (ref "C43") (pin "2") (pinfunction "2_2") (pintype "passive"))
      (node (ref "C44") (pin "1") (pinfunction "1_1") (pintype "passive"))
      (node (ref "R14") (pin "2") (pinfunction "2_2") (pintype "passive"))
      (node (ref "R17") (pin "2") (pinfunction "2_2") (pintype "passive"))
      (node (ref "U4") (pin "6") (pinfunction "PD_6") (pintype "input"))
    )
    (net (code "41") (name "Net-(U5-J1)") (class "Default")
      (node (ref "C37") (pin "2") (pinfunction "2_2") (pintype "passive"))
      (node (ref "U5") (pin "5") (pinfunction "J1_5") (pintype "bidirectional"))
    )
    (net (code "42") (name "Net-(U5-J2)") (class "Default")
      (node (ref "C30") (pin "1") (pinfunction "1_1") (pintype "passive"))
      (node (ref "U5") (pin "3") (pinfunction "J2_3") (pintype "bidirectional"))
    )
    (net (code "43") (name "Net-(U5-J3)") (class "Default")
      (node (ref "C31") (pin "1") (pinfunction "1_1") (pintype "passive"))
      (node (ref "U5") (pin "1") (pinfunction "J3_1") (pintype "bidirectional"))
    )
    (net (code "44") (name "Net-(U7-HOLD)") (class "Default")
      (node (ref "C50") (pin "1") (pinfunction "1_1") (pintype "passive"))
      (node (ref "L1") (pin "1") (pinfunction "1_1") (pintype "passive"))
      (node (ref "U7") (pin "3") (pinfunction "WP_3") (pintype "bidirectional"))
      (node (ref "U7") (pin "7") (pinfunction "HOLD_7") (pintype "bidirectional"))
      (node (ref "U7") (pin "8") (pinfunction "VCC_8") (pintype "power_in"))
    )
    (net (code "45") (name "Net-(X1-OUT)") (class "Default")
      (node (ref "C17") (pin "1") (pinfunction "1_1") (pintype "passive"))
      (node (ref "X1") (pin "3") (pinfunction "OUT_3") (pintype "bidirectional"))
    )
    (net (code "46") (name "PA_PD") (class "Default")
      (node (ref "R17") (pin "1") (pinfunction "1_1") (pintype "passive"))
      (node (ref "U3") (pin "7") (pinfunction "GPIO7_7") (pintype "bidirectional"))
    )
    (net (code "47") (name "PWR_EN") (class "Default")
      (node (ref "J15") (pin "1") (pinfunction "1_1") (pintype "passive"))
      (node (ref "R12") (pin "1") (pinfunction "1_1") (pintype "passive"))
      (node (ref "U1") (pin "3") (pinfunction "ON_3") (pintype "input"))
    )
    (net (code "48") (name "RESETB") (class "Default")
      (node (ref "J6") (pin "1") (pinfunction "1_1") (pintype "passive"))
      (node (ref "R8") (pin "2") (pinfunction "2_2") (pintype "passive"))
      (node (ref "U3") (pin "1") (pinfunction "RESETB_1") (pintype "bidirectional"))
    )
    (net (code "49") (name "RFG8") (class "Default")
      (node (ref "C22") (pin "2") (pinfunction "2_2") (pintype "passive"))
      (node (ref "K1") (pin "4") (pinfunction "DRAIN_2_4") (pintype "bidirectional"))
      (node (ref "R7") (pin "1") (pinfunction "1_1") (pintype "passive"))
      (node (ref "U4") (pin "12") (pinfunction "G8_12") (pintype "input"))
    )
    (net (code "50") (name "RF_RX") (class "Default")
      (node (ref "C29") (pin "P$2") (pinfunction "2_P$2") (pintype "passive"))
      (node (ref "C30") (pin "2") (pinfunction "2_2") (pintype "passive"))
      (node (ref "L12") (pin "P$2") (pinfunction "2_P$2") (pintype "passive"))
    )
    (net (code "51") (name "RF_TX") (class "Default")
      (node (ref "C28") (pin "2") (pinfunction "2_2") (pintype "passive"))
      (node (ref "C31") (pin "2") (pinfunction "2_2") (pintype "passive"))
      (node (ref "L8") (pin "P$2") (pinfunction "2_P$2") (pintype "passive"))
    )
    (net (code "52") (name "RXSW") (class "Default")
      (node (ref "C36") (pin "1") (pinfunction "1_1") (pintype "passive"))
      (node (ref "U3") (pin "22") (pinfunction "RXSW_22") (pintype "bidirectional"))
      (node (ref "U5") (pin "6") (pinfunction "V2_6") (pintype "power_in"))
    )
    (net (code "53") (name "SCLK") (class "Default")
      (node (ref "J8") (pin "1") (pinfunction "1_1") (pintype "passive"))
      (node (ref "U3") (pin "3") (pinfunction "SCLK_3") (pintype "bidirectional"))
    )
    (net (code "54") (name "TXSW") (class "Default")
      (node (ref "C42") (pin "1") (pinfunction "1_1") (pintype "passive"))
      (node (ref "U3") (pin "21") (pinfunction "TXSW_21") (pintype "bidirectional"))
      (node (ref "U5") (pin "4") (pinfunction "V1_4") (pintype "power_in"))
    )
    (net (code "55") (name "VDD") (class "Default")
      (node (ref "C14") (pin "1") (pinfunction "1_1") (pintype "passive"))
      (node (ref "C16") (pin "1") (pinfunction "1_1") (pintype "passive"))
      (node (ref "C19") (pin "1") (pinfunction "1_1") (pintype "passive"))
      (node (ref "C3") (pin "1") (pinfunction "1_1") (pintype "passive"))
      (node (ref "C45") (pin "1") (pinfunction "1_1") (pintype "passive"))
      (node (ref "C46") (pin "1") (pinfunction "1_1") (pintype "passive"))
      (node (ref "C49") (pin "1") (pinfunction "1_1") (pintype "passive"))
      (node (ref "J17") (pin "1") (pinfunction "1_1") (pintype "passive"))
      (node (ref "L10") (pin "2") (pinfunction "2_2") (pintype "passive"))
      (node (ref "L15") (pin "2") (pinfunction "2_2") (pintype "passive"))
      (node (ref "L3") (pin "2") (pinfunction "2_2") (pintype "passive"))
      (node (ref "L6") (pin "P$1") (pinfunction "1_P$1") (pintype "passive"))
      (node (ref "Q2") (pin "2") (pinfunction "S_2") (pintype "bidirectional"))
      (node (ref "R3") (pin "2") (pinfunction "2_2") (pintype "passive"))
      (node (ref "U2") (pin "1") (pinfunction "IN_1") (pintype "input"))
      (node (ref "U2") (pin "3") (pinfunction "EN_3") (pintype "input"))
      (node (ref "U6") (pin "1") (pinfunction "IN_1") (pintype "input"))
      (node (ref "U6") (pin "3") (pinfunction "EN_3") (pintype "input"))
    )
    (net (code "56") (name "VIN") (class "Default")
      (node (ref "C1") (pin "1") (pinfunction "1_1") (pintype "passive"))
      (node (ref "C48") (pin "1") (pinfunction "1_1") (pintype "passive"))
      (node (ref "J14") (pin "1") (pinfunction "1_1") (pintype "passive"))
      (node (ref "R9") (pin "2") (pinfunction "2_2") (pintype "passive"))
      (node (ref "U1") (pin "6") (pinfunction "VCC_6") (pintype "power_in"))
    )
    (net (code "57") (name "VREF1") (class "Default")
      (node (ref "C20") (pin "2") (pinfunction "2_2") (pintype "passive"))
      (node (ref "C21") (pin "2") (pinfunction "2_2") (pintype "passive"))
      (node (ref "J2") (pin "1") (pinfunction "1_1") (pintype "passive"))
      (node (ref "K1") (pin "3") (pinfunction "DRAIN_1_3") (pintype "bidirectional"))
      (node (ref "U4") (pin "13") (pinfunction "G16_13") (pintype "input"))
      (node (ref "U4") (pin "16") (pinfunction "VBIAS_16") (pintype "power_in"))
      (node (ref "U6") (pin "5") (pinfunction "OUT_5") (pintype "passive"))
    )
    (net (code "58") (name "unconnected-(U2-NC-Pad4)") (class "Default")
      (node (ref "U2") (pin "4") (pinfunction "NC_4") (pintype "no_connect"))
    )
    (net (code "59") (name "unconnected-(U3-GPIO0-Pad19)") (class "Default")
      (node (ref "U3") (pin "19") (pinfunction "GPIO0_19") (pintype "bidirectional"))
    )
    (net (code "60") (name "unconnected-(U3-GPIO1-Pad18)") (class "Default")
      (node (ref "U3") (pin "18") (pinfunction "GPIO1_18") (pintype "bidirectional"))
    )
    (net (code "61") (name "unconnected-(U3-GPIO2-Pad17)") (class "Default")
      (node (ref "U3") (pin "17") (pinfunction "GPIO2_17") (pintype "bidirectional"))
    )
    (net (code "62") (name "unconnected-(U3-GPIO3-Pad16)") (class "Default")
      (node (ref "U3") (pin "16") (pinfunction "GPIO3_16") (pintype "bidirectional"))
    )
    (net (code "63") (name "unconnected-(U3-GPIO4-Pad11)") (class "Default")
      (node (ref "U3") (pin "11") (pinfunction "GPIO4_11") (pintype "bidirectional"))
    )
    (net (code "64") (name "unconnected-(U3-GPIO5-Pad10)") (class "Default")
      (node (ref "U3") (pin "10") (pinfunction "GPIO5_10") (pintype "bidirectional"))
    )
    (net (code "65") (name "unconnected-(U3-GPIO6-Pad8)") (class "Default")
      (node (ref "U3") (pin "8") (pinfunction "GPIO6_8") (pintype "bidirectional"))
    )
    (net (code "66") (name "unconnected-(U3-NC-Pad42)") (class "Default")
      (node (ref "U3") (pin "42") (pinfunction "NC_42") (pintype "no_connect"))
    )
    (net (code "67") (name "unconnected-(U3-NC-Pad43)") (class "Default")
      (node (ref "U3") (pin "43") (pinfunction "NC_43") (pintype "no_connect"))
    )
    (net (code "68") (name "unconnected-(U3-NC-Pad44)") (class "Default")
      (node (ref "U3") (pin "44") (pinfunction "NC_44") (pintype "no_connect"))
    )
    (net (code "69") (name "unconnected-(U3-NC-Pad45)") (class "Default")
      (node (ref "U3") (pin "45") (pinfunction "NC_45") (pintype "no_connect"))
    )
    (net (code "70") (name "unconnected-(U4-NC-Pad1)") (class "Default")
      (node (ref "U4") (pin "1") (pinfunction "NC_1") (pintype "no_connect"))
    )
    (net (code "71") (name "unconnected-(U4-NC-Pad4)") (class "Default")
      (node (ref "U4") (pin "4") (pinfunction "NC_4") (pintype "no_connect"))
    )
    (net (code "72") (name "unconnected-(U4-NC-Pad5)") (class "Default")
      (node (ref "U4") (pin "5") (pinfunction "NC_5") (pintype "no_connect"))
    )
    (net (code "73") (name "unconnected-(U4-NC-Pad7)") (class "Default")
      (node (ref "U4") (pin "7") (pinfunction "NC_7") (pintype "no_connect"))
    )
    (net (code "74") (name "unconnected-(U4-NC-Pad8)") (class "Default")
      (node (ref "U4") (pin "8") (pinfunction "NC_8") (pintype "no_connect"))
    )
    (net (code "75") (name "unconnected-(U4-NC-Pad11)") (class "Default")
      (node (ref "U4") (pin "11") (pinfunction "NC_11") (pintype "no_connect"))
    )
    (net (code "76") (name "unconnected-(U4-NC-Pad15)") (class "Default")
      (node (ref "U4") (pin "15") (pinfunction "NC_15") (pintype "no_connect"))
    )
    (net (code "77") (name "unconnected-(U6-NC-Pad4)") (class "Default")
      (node (ref "U6") (pin "4") (pinfunction "NC_4") (pintype "no_connect"))
    )
  )
)
